# Main.net
KiCad netlist of a schematic drawn in Altium Designer
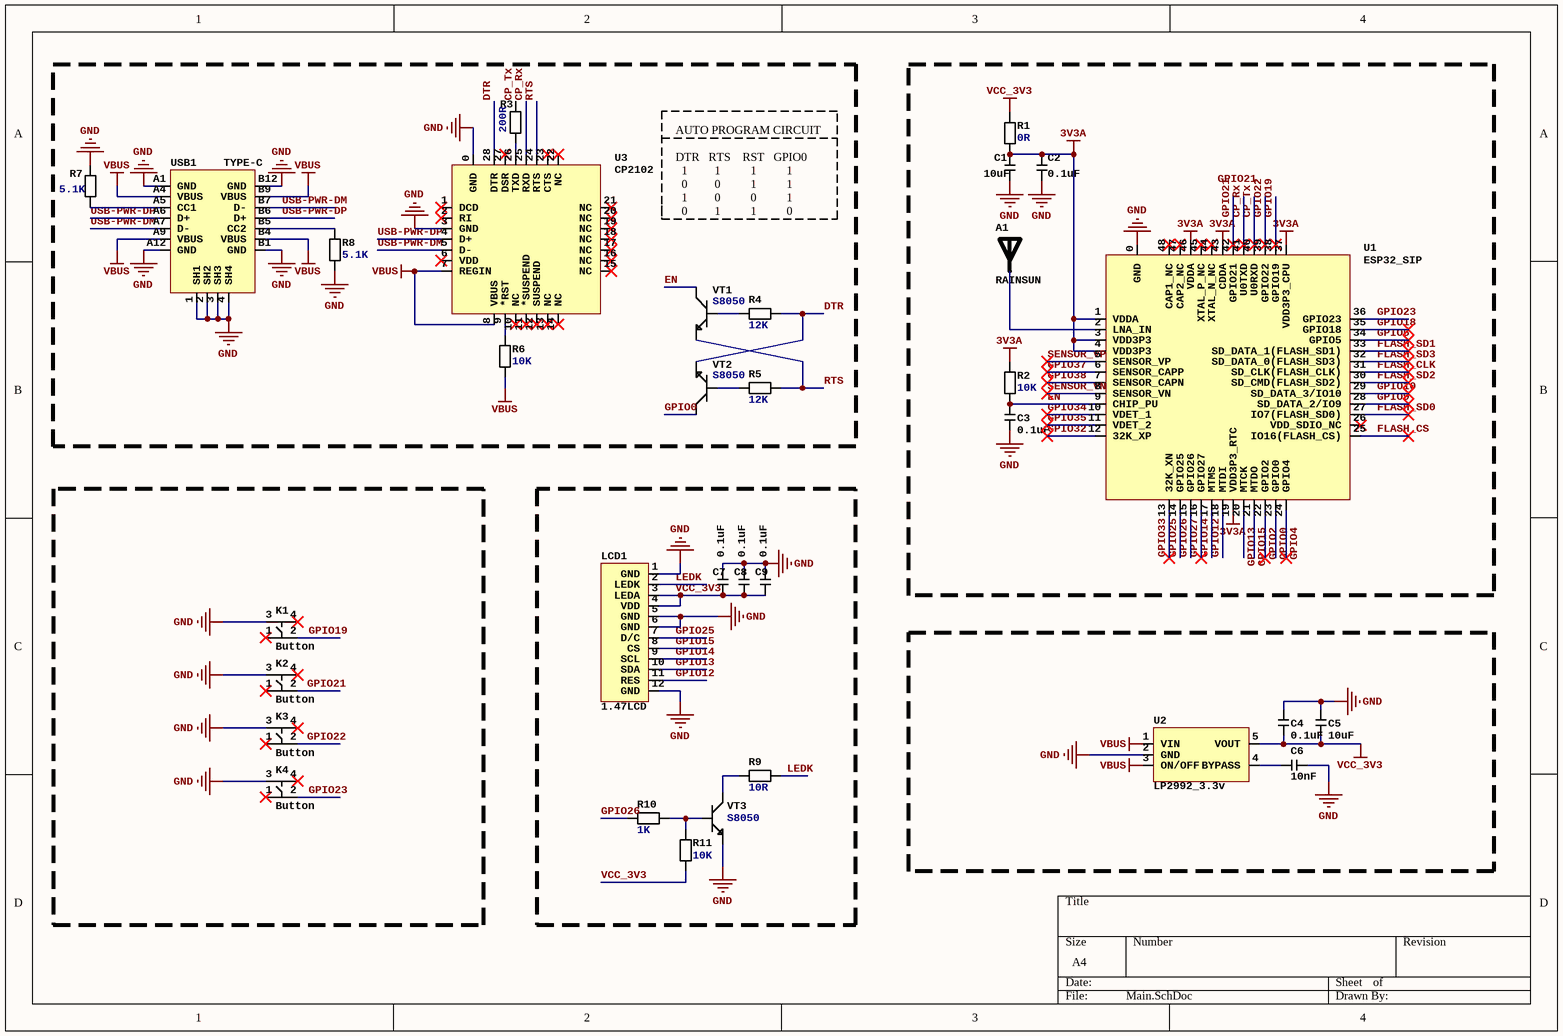
[diagram p0: Main.SchDoc]

(export (version "E")
  (design (tool "Eeschema 10.0.6"))
  (components
    (comp (ref "A1")
      (value "RAINSUN")
      (footprint "ANT-Rainsun-AN5120")
      (libsource (lib "ESP32-Pico-Pill") (part "ANT-Rainsun-AP5120"))
    )
    (comp (ref "C1")
      (value "10uF")
      (footprint "CAP_0603")
      (libsource (lib "ESP32-Pico-Pill") (part "CAP_0603_10uF"))
    )
    (comp (ref "C2")
      (value "0.1uF")
      (footprint "CAP_0603")
      (libsource (lib "ESP32-Pico-Pill") (part "CAP_0603_0.1uF"))
    )
    (comp (ref "C3")
      (value "0.1uF")
      (footprint "CAP_0603")
      (libsource (lib "ESP32-Pico-Pill") (part "CAP_0603_0.1uF"))
    )
    (comp (ref "C4")
      (value "0.1uF")
      (footprint "CAP_0603")
      (libsource (lib "ESP32-Pico-Pill") (part "CAP_0603_0.1uF"))
    )
    (comp (ref "C5")
      (value "10uF")
      (footprint "CAP_0603")
      (libsource (lib "ESP32-Pico-Pill") (part "CAP_0603_10uF"))
    )
    (comp (ref "C6")
      (value "10nF")
      (footprint "CAP_0603")
      (libsource (lib "ESP32-Pico-Pill") (part "CAP_0603_10nF"))
    )
    (comp (ref "C7")
      (value "0.1uF")
      (footprint "CAP_0603")
      (libsource (lib "ESP32-Pico-Pill") (part "CAP_0603_0.1uF"))
    )
    (comp (ref "C8")
      (value "0.1uF")
      (footprint "CAP_0603")
      (libsource (lib "ESP32-Pico-Pill") (part "CAP_0603_0.1uF"))
    )
    (comp (ref "C9")
      (value "0.1uF")
      (footprint "CAP_0603")
      (libsource (lib "ESP32-Pico-Pill") (part "CAP_0603_0.1uF"))
    )
    (comp (ref "K1")
      (value "Button")
      (footprint "Button")
      (description "中乌龟4.8x3.6x4.6mm")
      (libsource (lib "ESP32-Pico-Pill") (part "Button"))
    )
    (comp (ref "K2")
      (value "Button")
      (footprint "Button")
      (description "中乌龟4.8x3.6x4.6mm")
      (libsource (lib "ESP32-Pico-Pill") (part "Button"))
    )
    (comp (ref "K3")
      (value "Button")
      (footprint "Button")
      (description "中乌龟4.8x3.6x4.6mm")
      (libsource (lib "ESP32-Pico-Pill") (part "Button"))
    )
    (comp (ref "K4")
      (value "Button")
      (footprint "Button")
      (description "中乌龟4.8x3.6x4.6mm")
      (libsource (lib "ESP32-Pico-Pill") (part "Button"))
    )
    (comp (ref "LCD1")
      (value "1.47LCD")
      (footprint "IPS130-12")
      (libsource (lib "ESP32-Pico-Pill") (part "1.47LCD"))
    )
    (comp (ref "R1")
      (value "0R")
      (footprint "RES_0603")
      (libsource (lib "ESP32-Pico-Pill") (part "RES_0603_0R"))
    )
    (comp (ref "R2")
      (value "10K")
      (footprint "RES_0603")
      (libsource (lib "ESP32-Pico-Pill") (part "RES_0603_10K"))
    )
    (comp (ref "R3")
      (value "200R")
      (footprint "RES_0603")
      (libsource (lib "ESP32-Pico-Pill") (part "RES_0603_200R"))
    )
    (comp (ref "R4")
      (value "12K")
      (footprint "RES_0603")
      (libsource (lib "ESP32-Pico-Pill") (part "RES_0603_12K"))
    )
    (comp (ref "R5")
      (value "12K")
      (footprint "RES_0603")
      (libsource (lib "ESP32-Pico-Pill") (part "RES_0603_12K"))
    )
    (comp (ref "R6")
      (value "10K")
      (footprint "RES_0603")
      (libsource (lib "ESP32-Pico-Pill") (part "RES_0603_10K"))
    )
    (comp (ref "R7")
      (value "5.1K")
      (footprint "RES_0603")
      (libsource (lib "ESP32-Pico-Pill") (part "RES_0603_5.1K"))
    )
    (comp (ref "R8")
      (value "5.1K")
      (footprint "RES_0603")
      (libsource (lib "ESP32-Pico-Pill") (part "RES_0603_5.1K"))
    )
    (comp (ref "R9")
      (value "10R")
      (footprint "RES_0603")
      (libsource (lib "ESP32-Pico-Pill") (part "RES_0603_10R"))
    )
    (comp (ref "R10")
      (value "1K")
      (footprint "RES_0603")
      (libsource (lib "ESP32-Pico-Pill") (part "RES_0603_1K"))
    )
    (comp (ref "R11")
      (value "10K")
      (footprint "RES_0603")
      (libsource (lib "ESP32-Pico-Pill") (part "RES_0603_10K"))
    )
    (comp (ref "U1")
      (value "ESP32_SIP")
      (footprint "ESP32-Pico")
      (libsource (lib "ESP32-Pico-Pill") (part "ESP32-Pico-D4"))
    )
    (comp (ref "U2")
      (value "LP2992_3.3v")
      (footprint "LP2992")
      (libsource (lib "ESP32-Pico-Pill") (part "LP2992_3.3v"))
    )
    (comp (ref "U3")
      (value "CP2102")
      (footprint "CP2102")
      (libsource (lib "ESP32-Pico-Pill") (part "CP2102"))
    )
    (comp (ref "USB1")
      (value "TYPE-C")
      (footprint "TYPE-C")
      (description "TYPE-C  16P")
      (libsource (lib "ESP32-Pico-Pill") (part "TYPE-C"))
    )
    (comp (ref "VT1")
      (value "S8050")
      (footprint "s8050")
      (description "SOT23")
      (libsource (lib "ESP32-Pico-Pill") (part "S8050"))
    )
    (comp (ref "VT2")
      (value "S8050")
      (footprint "s8050")
      (description "SOT23")
      (libsource (lib "ESP32-Pico-Pill") (part "S8050"))
    )
    (comp (ref "VT3")
      (value "S8050")
      (footprint "s8050")
      (description "SOT23")
      (libsource (lib "ESP32-Pico-Pill") (part "S8050"))
    )
  )
  (nets
    (net (code "1") (name "/CP_Rx") (class "Default")
      (node (ref "U1") (pin "41") (pinfunction "U0TXD_41") (pintype "passive"))
      (node (ref "U3") (pin "25") (pinfunction "RXD_25") (pintype "passive"))
    )
    (net (code "2") (name "/CP_Tx") (class "Default")
      (node (ref "R3") (pin "2") (pinfunction "2_2") (pintype "passive"))
      (node (ref "U1") (pin "40") (pinfunction "U0RXD_40") (pintype "passive"))
    )
    (net (code "3") (name "/DTR") (class "Default")
      (node (ref "R4") (pin "2") (pinfunction "2_2") (pintype "passive"))
      (node (ref "U3") (pin "28") (pinfunction "DTR_28") (pintype "passive"))
      (node (ref "VT2") (pin "2") (pinfunction "E_2") (pintype "passive"))
    )
    (net (code "4") (name "/EN") (class "Default")
      (node (ref "C3") (pin "2") (pinfunction "2_2") (pintype "passive"))
      (node (ref "R2") (pin "1") (pinfunction "1_1") (pintype "passive"))
      (node (ref "U1") (pin "9") (pinfunction "CHIP_PU_9") (pintype "passive"))
      (node (ref "VT1") (pin "1") (pinfunction "C_1") (pintype "passive"))
    )
    (net (code "5") (name "/FLASH_CLK") (class "Default")
      (node (ref "U1") (pin "31") (pinfunction "SD_CLK(FLASH_CLK)_31") (pintype "passive+no_connect"))
    )
    (net (code "6") (name "/FLASH_CS") (class "Default")
      (node (ref "U1") (pin "25") (pinfunction "IO16(FLASH_CS)_25") (pintype "passive+no_connect"))
    )
    (net (code "7") (name "/FLASH_SD0") (class "Default")
      (node (ref "U1") (pin "27") (pinfunction "IO7(FLASH_SD0)_27") (pintype "passive+no_connect"))
    )
    (net (code "8") (name "/FLASH_SD1") (class "Default")
      (node (ref "U1") (pin "33") (pinfunction "SD_DATA_1(FLASH_SD1)_33") (pintype "passive+no_connect"))
    )
    (net (code "9") (name "/FLASH_SD2") (class "Default")
      (node (ref "U1") (pin "30") (pinfunction "SD_CMD(FLASH_SD2)_30") (pintype "passive+no_connect"))
    )
    (net (code "10") (name "/FLASH_SD3") (class "Default")
      (node (ref "U1") (pin "32") (pinfunction "SD_DATA_0(FLASH_SD3)_32") (pintype "passive+no_connect"))
    )
    (net (code "11") (name "/GPIO0") (class "Default")
      (node (ref "U1") (pin "23") (pinfunction "GPIO0_23") (pintype "passive"))
      (node (ref "VT2") (pin "1") (pinfunction "C_1") (pintype "passive"))
    )
    (net (code "12") (name "/GPIO2") (class "Default")
      (node (ref "U1") (pin "22") (pinfunction "GPIO2_22") (pintype "passive+no_connect"))
    )
    (net (code "13") (name "/GPIO4") (class "Default")
      (node (ref "U1") (pin "24") (pinfunction "GPIO4_24") (pintype "passive+no_connect"))
    )
    (net (code "14") (name "/GPIO5") (class "Default")
      (node (ref "U1") (pin "34") (pinfunction "GPIO5_34") (pintype "passive+no_connect"))
    )
    (net (code "15") (name "/GPIO9") (class "Default")
      (node (ref "U1") (pin "28") (pinfunction "SD_DATA_2/IO9_28") (pintype "passive+no_connect"))
    )
    (net (code "16") (name "/GPIO10") (class "Default")
      (node (ref "U1") (pin "29") (pinfunction "SD_DATA_3/IO10_29") (pintype "passive+no_connect"))
    )
    (net (code "17") (name "/GPIO12") (class "Default")
      (node (ref "LCD1") (pin "11") (pinfunction "RES_11") (pintype "passive"))
      (node (ref "U1") (pin "18") (pinfunction "MTDI_18") (pintype "passive"))
    )
    (net (code "18") (name "/GPIO13") (class "Default")
      (node (ref "LCD1") (pin "10") (pinfunction "SDA_10") (pintype "passive"))
      (node (ref "U1") (pin "20") (pinfunction "MTCK_20") (pintype "passive"))
    )
    (net (code "19") (name "/GPIO14") (class "Default")
      (node (ref "LCD1") (pin "9") (pinfunction "SCL_9") (pintype "passive"))
      (node (ref "U1") (pin "17") (pinfunction "MTMS_17") (pintype "passive"))
    )
    (net (code "20") (name "/GPIO15") (class "Default")
      (node (ref "LCD1") (pin "8") (pinfunction "CS_8") (pintype "passive"))
      (node (ref "U1") (pin "21") (pinfunction "MTDO_21") (pintype "passive"))
    )
    (net (code "21") (name "/GPIO18") (class "Default")
      (node (ref "U1") (pin "35") (pinfunction "GPIO18_35") (pintype "passive+no_connect"))
    )
    (net (code "22") (name "/GPIO19") (class "Default")
      (node (ref "K1") (pin "2") (pinfunction "2_2") (pintype "passive"))
      (node (ref "U1") (pin "38") (pinfunction "GPIO19_38") (pintype "passive"))
    )
    (net (code "23") (name "/GPIO21") (class "Default")
      (node (ref "K2") (pin "2") (pinfunction "2_2") (pintype "passive"))
      (node (ref "U1") (pin "42") (pinfunction "GPIO21_42") (pintype "passive"))
    )
    (net (code "24") (name "/GPIO22") (class "Default")
      (node (ref "K3") (pin "2") (pinfunction "2_2") (pintype "passive"))
      (node (ref "U1") (pin "39") (pinfunction "GPIO22_39") (pintype "passive"))
    )
    (net (code "25") (name "/GPIO23") (class "Default")
      (node (ref "K4") (pin "2") (pinfunction "2_2") (pintype "passive"))
      (node (ref "U1") (pin "36") (pinfunction "GPIO23_36") (pintype "passive"))
    )
    (net (code "26") (name "/GPIO25") (class "Default")
      (node (ref "LCD1") (pin "7") (pinfunction "D/C_7") (pintype "passive"))
      (node (ref "U1") (pin "14") (pinfunction "GPIO25_14") (pintype "passive"))
    )
    (net (code "27") (name "/GPIO26") (class "Default")
      (node (ref "R10") (pin "1") (pinfunction "1_1") (pintype "passive"))
      (node (ref "U1") (pin "15") (pinfunction "GPIO26_15") (pintype "passive"))
    )
    (net (code "28") (name "/GPIO27") (class "Default")
      (node (ref "U1") (pin "16") (pinfunction "GPIO27_16") (pintype "passive+no_connect"))
    )
    (net (code "29") (name "/GPIO32") (class "Default")
      (node (ref "U1") (pin "12") (pinfunction "32K_XP_12") (pintype "passive+no_connect"))
    )
    (net (code "30") (name "/GPIO33") (class "Default")
      (node (ref "U1") (pin "13") (pinfunction "32K_XN_13") (pintype "passive+no_connect"))
    )
    (net (code "31") (name "/GPIO34") (class "Default")
      (node (ref "U1") (pin "10") (pinfunction "VDET_1_10") (pintype "passive+no_connect"))
    )
    (net (code "32") (name "/GPIO35") (class "Default")
      (node (ref "U1") (pin "11") (pinfunction "VDET_2_11") (pintype "passive+no_connect"))
    )
    (net (code "33") (name "/GPIO37") (class "Default")
      (node (ref "U1") (pin "6") (pinfunction "SENSOR_CAPP_6") (pintype "passive+no_connect"))
    )
    (net (code "34") (name "/GPIO38") (class "Default")
      (node (ref "U1") (pin "7") (pinfunction "SENSOR_CAPN_7") (pintype "passive+no_connect"))
    )
    (net (code "35") (name "/LEDK") (class "Default")
      (node (ref "LCD1") (pin "2") (pinfunction "LEDK_2") (pintype "passive"))
      (node (ref "R9") (pin "2") (pinfunction "2_2") (pintype "passive"))
    )
    (net (code "36") (name "/RTS") (class "Default")
      (node (ref "R5") (pin "2") (pinfunction "2_2") (pintype "passive"))
      (node (ref "U3") (pin "24") (pinfunction "RTS_24") (pintype "passive"))
      (node (ref "VT1") (pin "2") (pinfunction "E_2") (pintype "passive"))
    )
    (net (code "37") (name "/SENSOR_VN") (class "Default")
      (node (ref "U1") (pin "8") (pinfunction "SENSOR_VN_8") (pintype "passive+no_connect"))
    )
    (net (code "38") (name "/SENSOR_VP") (class "Default")
      (node (ref "U1") (pin "5") (pinfunction "SENSOR_VP_5") (pintype "passive+no_connect"))
    )
    (net (code "39") (name "/USB-PWR-DM") (class "Default")
      (node (ref "U3") (pin "5") (pinfunction "D-_5") (pintype "passive"))
      (node (ref "USB1") (pin "A7") (pinfunction "D-_A7") (pintype "passive"))
      (node (ref "USB1") (pin "B7") (pinfunction "D-_B7") (pintype "passive"))
    )
    (net (code "40") (name "/USB-PWR-DP") (class "Default")
      (node (ref "U3") (pin "4") (pinfunction "D+_4") (pintype "passive"))
      (node (ref "USB1") (pin "A6") (pinfunction "D+_A6") (pintype "passive"))
      (node (ref "USB1") (pin "B6") (pinfunction "D+_B6") (pintype "passive"))
    )
    (net (code "41") (name "3V3A") (class "Default")
      (node (ref "C1") (pin "2") (pinfunction "2_2") (pintype "passive"))
      (node (ref "C2") (pin "2") (pinfunction "2_2") (pintype "passive"))
      (node (ref "R1") (pin "1") (pinfunction "1_1") (pintype "passive"))
      (node (ref "R2") (pin "2") (pinfunction "2_2") (pintype "passive"))
      (node (ref "U1") (pin "1") (pinfunction "VDDA_1") (pintype "passive"))
      (node (ref "U1") (pin "19") (pinfunction "VDD3P3_RTC_19") (pintype "passive"))
      (node (ref "U1") (pin "3") (pinfunction "VDD3P3_3") (pintype "passive"))
      (node (ref "U1") (pin "37") (pinfunction "VDD3P3_CPU_37") (pintype "passive"))
      (node (ref "U1") (pin "4") (pinfunction "VDD3P3_4") (pintype "passive"))
      (node (ref "U1") (pin "43") (pinfunction "CDDA_43") (pintype "passive"))
      (node (ref "U1") (pin "46") (pinfunction "VDDA_46") (pintype "passive"))
    )
    (net (code "42") (name "GND") (class "Default")
      (node (ref "C1") (pin "1") (pinfunction "1_1") (pintype "passive"))
      (node (ref "C2") (pin "1") (pinfunction "1_1") (pintype "passive"))
      (node (ref "C3") (pin "1") (pinfunction "1_1") (pintype "passive"))
      (node (ref "C4") (pin "2") (pinfunction "2_2") (pintype "passive"))
      (node (ref "C5") (pin "2") (pinfunction "2_2") (pintype "passive"))
      (node (ref "C6") (pin "2") (pinfunction "2_2") (pintype "passive"))
      (node (ref "C7") (pin "2") (pinfunction "2_2") (pintype "passive"))
      (node (ref "C8") (pin "2") (pinfunction "2_2") (pintype "passive"))
      (node (ref "C9") (pin "2") (pinfunction "2_2") (pintype "passive"))
      (node (ref "K1") (pin "3") (pinfunction "3_3") (pintype "passive"))
      (node (ref "K2") (pin "3") (pinfunction "3_3") (pintype "passive"))
      (node (ref "K3") (pin "3") (pinfunction "3_3") (pintype "passive"))
      (node (ref "K4") (pin "3") (pinfunction "3_3") (pintype "passive"))
      (node (ref "LCD1") (pin "1") (pinfunction "GND_1") (pintype "passive"))
      (node (ref "LCD1") (pin "12") (pinfunction "GND_12") (pintype "passive"))
      (node (ref "LCD1") (pin "5") (pinfunction "GND_5") (pintype "passive"))
      (node (ref "LCD1") (pin "6") (pinfunction "GND_6") (pintype "passive"))
      (node (ref "R7") (pin "2") (pinfunction "2_2") (pintype "passive"))
      (node (ref "R8") (pin "1") (pinfunction "1_1") (pintype "passive"))
      (node (ref "U1") (pin "0") (pinfunction "GND_0") (pintype "passive"))
      (node (ref "U2") (pin "2") (pinfunction "GND_2") (pintype "passive"))
      (node (ref "U3") (pin "0") (pinfunction "GND_0") (pintype "passive"))
      (node (ref "U3") (pin "3") (pinfunction "GND_3") (pintype "passive"))
      (node (ref "USB1") (pin "1") (pinfunction "SH1_1") (pintype "passive"))
      (node (ref "USB1") (pin "2") (pinfunction "SH2_2") (pintype "passive"))
      (node (ref "USB1") (pin "3") (pinfunction "SH3_3") (pintype "passive"))
      (node (ref "USB1") (pin "4") (pinfunction "SH4_4") (pintype "passive"))
      (node (ref "USB1") (pin "A1") (pinfunction "GND_A1") (pintype "passive"))
      (node (ref "USB1") (pin "A12") (pinfunction "GND_A12") (pintype "passive"))
      (node (ref "USB1") (pin "B1") (pinfunction "GND_B1") (pintype "passive"))
      (node (ref "USB1") (pin "B12") (pinfunction "GND_B12") (pintype "passive"))
      (node (ref "VT3") (pin "2") (pinfunction "E_2") (pintype "passive"))
    )
    (net (code "43") (name "Net-(U1-LNA_IN)") (class "Default")
      (node (ref "A1") (pin "1") (pinfunction "1_1") (pintype "passive"))
      (node (ref "U1") (pin "2") (pinfunction "LNA_IN_2") (pintype "passive"))
    )
    (net (code "44") (name "Net-(U2-BYPASS)") (class "Default")
      (node (ref "C6") (pin "1") (pinfunction "1_1") (pintype "passive"))
      (node (ref "U2") (pin "4") (pinfunction "BYPASS_4") (pintype "passive"))
    )
    (net (code "45") (name "Net-(U3-*RST)") (class "Default")
      (node (ref "R6") (pin "2") (pinfunction "2_2") (pintype "passive"))
      (node (ref "U3") (pin "9") (pinfunction "*RST_9") (pintype "passive"))
    )
    (net (code "46") (name "Net-(U3-TXD)") (class "Default")
      (node (ref "R3") (pin "1") (pinfunction "1_1") (pintype "passive"))
      (node (ref "U3") (pin "26") (pinfunction "TXD_26") (pintype "passive"))
    )
    (net (code "47") (name "Net-(USB1-CC1)") (class "Default")
      (node (ref "R7") (pin "1") (pinfunction "1_1") (pintype "passive"))
      (node (ref "USB1") (pin "A5") (pinfunction "CC1_A5") (pintype "passive"))
    )
    (net (code "48") (name "Net-(USB1-CC2)") (class "Default")
      (node (ref "R8") (pin "2") (pinfunction "2_2") (pintype "passive"))
      (node (ref "USB1") (pin "B5") (pinfunction "CC2_B5") (pintype "passive"))
    )
    (net (code "49") (name "Net-(VT1-B)") (class "Default")
      (node (ref "R4") (pin "1") (pinfunction "1_1") (pintype "passive"))
      (node (ref "VT1") (pin "3") (pinfunction "B_3") (pintype "passive"))
    )
    (net (code "50") (name "Net-(VT2-B)") (class "Default")
      (node (ref "R5") (pin "1") (pinfunction "1_1") (pintype "passive"))
      (node (ref "VT2") (pin "3") (pinfunction "B_3") (pintype "passive"))
    )
    (net (code "51") (name "Net-(VT3-B)") (class "Default")
      (node (ref "R10") (pin "2") (pinfunction "2_2") (pintype "passive"))
      (node (ref "R11") (pin "2") (pinfunction "2_2") (pintype "passive"))
      (node (ref "VT3") (pin "3") (pinfunction "B_3") (pintype "passive"))
    )
    (net (code "52") (name "Net-(VT3-C)") (class "Default")
      (node (ref "R9") (pin "1") (pinfunction "1_1") (pintype "passive"))
      (node (ref "VT3") (pin "1") (pinfunction "C_1") (pintype "passive"))
    )
    (net (code "53") (name "VBUS") (class "Default")
      (node (ref "R6") (pin "1") (pinfunction "1_1") (pintype "passive"))
      (node (ref "U2") (pin "1") (pinfunction "VIN_1") (pintype "passive"))
      (node (ref "U2") (pin "3") (pinfunction "ON/OFF_3") (pintype "passive"))
      (node (ref "U3") (pin "7") (pinfunction "REGIN_7") (pintype "passive"))
      (node (ref "U3") (pin "8") (pinfunction "VBUS_8") (pintype "passive"))
      (node (ref "USB1") (pin "A4") (pinfunction "VBUS_A4") (pintype "passive"))
      (node (ref "USB1") (pin "A9") (pinfunction "VBUS_A9") (pintype "passive"))
      (node (ref "USB1") (pin "B4") (pinfunction "VBUS_B4") (pintype "passive"))
      (node (ref "USB1") (pin "B9") (pinfunction "VBUS_B9") (pintype "passive"))
    )
    (net (code "54") (name "VCC_3V3") (class "Default")
      (node (ref "C4") (pin "1") (pinfunction "1_1") (pintype "passive"))
      (node (ref "C5") (pin "1") (pinfunction "1_1") (pintype "passive"))
      (node (ref "C7") (pin "1") (pinfunction "1_1") (pintype "passive"))
      (node (ref "C8") (pin "1") (pinfunction "1_1") (pintype "passive"))
      (node (ref "C9") (pin "1") (pinfunction "1_1") (pintype "passive"))
      (node (ref "LCD1") (pin "3") (pinfunction "LEDA_3") (pintype "passive"))
      (node (ref "LCD1") (pin "4") (pinfunction "VDD_4") (pintype "passive"))
      (node (ref "R1") (pin "2") (pinfunction "2_2") (pintype "passive"))
      (node (ref "R11") (pin "1") (pinfunction "1_1") (pintype "passive"))
      (node (ref "U2") (pin "5") (pinfunction "VOUT_5") (pintype "passive"))
    )
    (net (code "55") (name "unconnected-(K1-Pad1)") (class "Default")
      (node (ref "K1") (pin "1") (pinfunction "1_1") (pintype "passive+no_connect"))
    )
    (net (code "56") (name "unconnected-(K1-Pad4)") (class "Default")
      (node (ref "K1") (pin "4") (pinfunction "4_4") (pintype "passive+no_connect"))
    )
    (net (code "57") (name "unconnected-(K2-Pad1)") (class "Default")
      (node (ref "K2") (pin "1") (pinfunction "1_1") (pintype "passive+no_connect"))
    )
    (net (code "58") (name "unconnected-(K2-Pad4)") (class "Default")
      (node (ref "K2") (pin "4") (pinfunction "4_4") (pintype "passive+no_connect"))
    )
    (net (code "59") (name "unconnected-(K3-Pad1)") (class "Default")
      (node (ref "K3") (pin "1") (pinfunction "1_1") (pintype "passive+no_connect"))
    )
    (net (code "60") (name "unconnected-(K3-Pad4)") (class "Default")
      (node (ref "K3") (pin "4") (pinfunction "4_4") (pintype "passive+no_connect"))
    )
    (net (code "61") (name "unconnected-(K4-Pad1)") (class "Default")
      (node (ref "K4") (pin "1") (pinfunction "1_1") (pintype "passive+no_connect"))
    )
    (net (code "62") (name "unconnected-(K4-Pad4)") (class "Default")
      (node (ref "K4") (pin "4") (pinfunction "4_4") (pintype "passive+no_connect"))
    )
    (net (code "63") (name "unconnected-(U1-CAP1_NC-Pad48)") (class "Default")
      (node (ref "U1") (pin "48") (pinfunction "CAP1_NC_48") (pintype "passive+no_connect"))
    )
    (net (code "64") (name "unconnected-(U1-CAP2_NC-Pad47)") (class "Default")
      (node (ref "U1") (pin "47") (pinfunction "CAP2_NC_47") (pintype "passive+no_connect"))
    )
    (net (code "65") (name "unconnected-(U1-VDD_SDIO_NC-Pad26)") (class "Default")
      (node (ref "U1") (pin "26") (pinfunction "VDD_SDIO_NC_26") (pintype "passive+no_connect"))
    )
    (net (code "66") (name "unconnected-(U1-XTAL_N_NC-Pad44)") (class "Default")
      (node (ref "U1") (pin "44") (pinfunction "XTAL_N_NC_44") (pintype "passive+no_connect"))
    )
    (net (code "67") (name "unconnected-(U1-XTAL_P_NC-Pad45)") (class "Default")
      (node (ref "U1") (pin "45") (pinfunction "XTAL_P_NC_45") (pintype "passive+no_connect"))
    )
    (net (code "68") (name "unconnected-(U3-*SUSPEND-Pad11)") (class "Default")
      (node (ref "U3") (pin "11") (pinfunction "*SUSPEND_11") (pintype "passive+no_connect"))
    )
    (net (code "69") (name "unconnected-(U3-CTS-Pad23)") (class "Default")
      (node (ref "U3") (pin "23") (pinfunction "CTS_23") (pintype "passive+no_connect"))
    )
    (net (code "70") (name "unconnected-(U3-DCD-Pad1)") (class "Default")
      (node (ref "U3") (pin "1") (pinfunction "DCD_1") (pintype "passive+no_connect"))
    )
    (net (code "71") (name "unconnected-(U3-DSR-Pad27)") (class "Default")
      (node (ref "U3") (pin "27") (pinfunction "DSR_27") (pintype "passive+no_connect"))
    )
    (net (code "72") (name "unconnected-(U3-NC-Pad10)") (class "Default")
      (node (ref "U3") (pin "10") (pinfunction "NC_10") (pintype "passive+no_connect"))
    )
    (net (code "73") (name "unconnected-(U3-NC-Pad13)") (class "Default")
      (node (ref "U3") (pin "13") (pinfunction "NC_13") (pintype "passive+no_connect"))
    )
    (net (code "74") (name "unconnected-(U3-NC-Pad14)") (class "Default")
      (node (ref "U3") (pin "14") (pinfunction "NC_14") (pintype "passive+no_connect"))
    )
    (net (code "75") (name "unconnected-(U3-NC-Pad15)") (class "Default")
      (node (ref "U3") (pin "15") (pinfunction "NC_15") (pintype "passive+no_connect"))
    )
    (net (code "76") (name "unconnected-(U3-NC-Pad16)") (class "Default")
      (node (ref "U3") (pin "16") (pinfunction "NC_16") (pintype "passive+no_connect"))
    )
    (net (code "77") (name "unconnected-(U3-NC-Pad17)") (class "Default")
      (node (ref "U3") (pin "17") (pinfunction "NC_17") (pintype "passive+no_connect"))
    )
    (net (code "78") (name "unconnected-(U3-NC-Pad18)") (class "Default")
      (node (ref "U3") (pin "18") (pinfunction "NC_18") (pintype "passive+no_connect"))
    )
    (net (code "79") (name "unconnected-(U3-NC-Pad19)") (class "Default")
      (node (ref "U3") (pin "19") (pinfunction "NC_19") (pintype "passive+no_connect"))
    )
    (net (code "80") (name "unconnected-(U3-NC-Pad20)") (class "Default")
      (node (ref "U3") (pin "20") (pinfunction "NC_20") (pintype "passive+no_connect"))
    )
    (net (code "81") (name "unconnected-(U3-NC-Pad21)") (class "Default")
      (node (ref "U3") (pin "21") (pinfunction "NC_21") (pintype "passive+no_connect"))
    )
    (net (code "82") (name "unconnected-(U3-NC-Pad22)") (class "Default")
      (node (ref "U3") (pin "22") (pinfunction "NC_22") (pintype "passive+no_connect"))
    )
    (net (code "83") (name "unconnected-(U3-RI-Pad2)") (class "Default")
      (node (ref "U3") (pin "2") (pinfunction "RI_2") (pintype "passive+no_connect"))
    )
    (net (code "84") (name "unconnected-(U3-SUSPEND-Pad12)") (class "Default")
      (node (ref "U3") (pin "12") (pinfunction "SUSPEND_12") (pintype "passive+no_connect"))
    )
    (net (code "85") (name "unconnected-(U3-VDD-Pad6)") (class "Default")
      (node (ref "U3") (pin "6") (pinfunction "VDD_6") (pintype "passive+no_connect"))
    )
  )
)
